# PIN_Gamma.net
KiCad netlist of a schematic drawn in Altium Designer
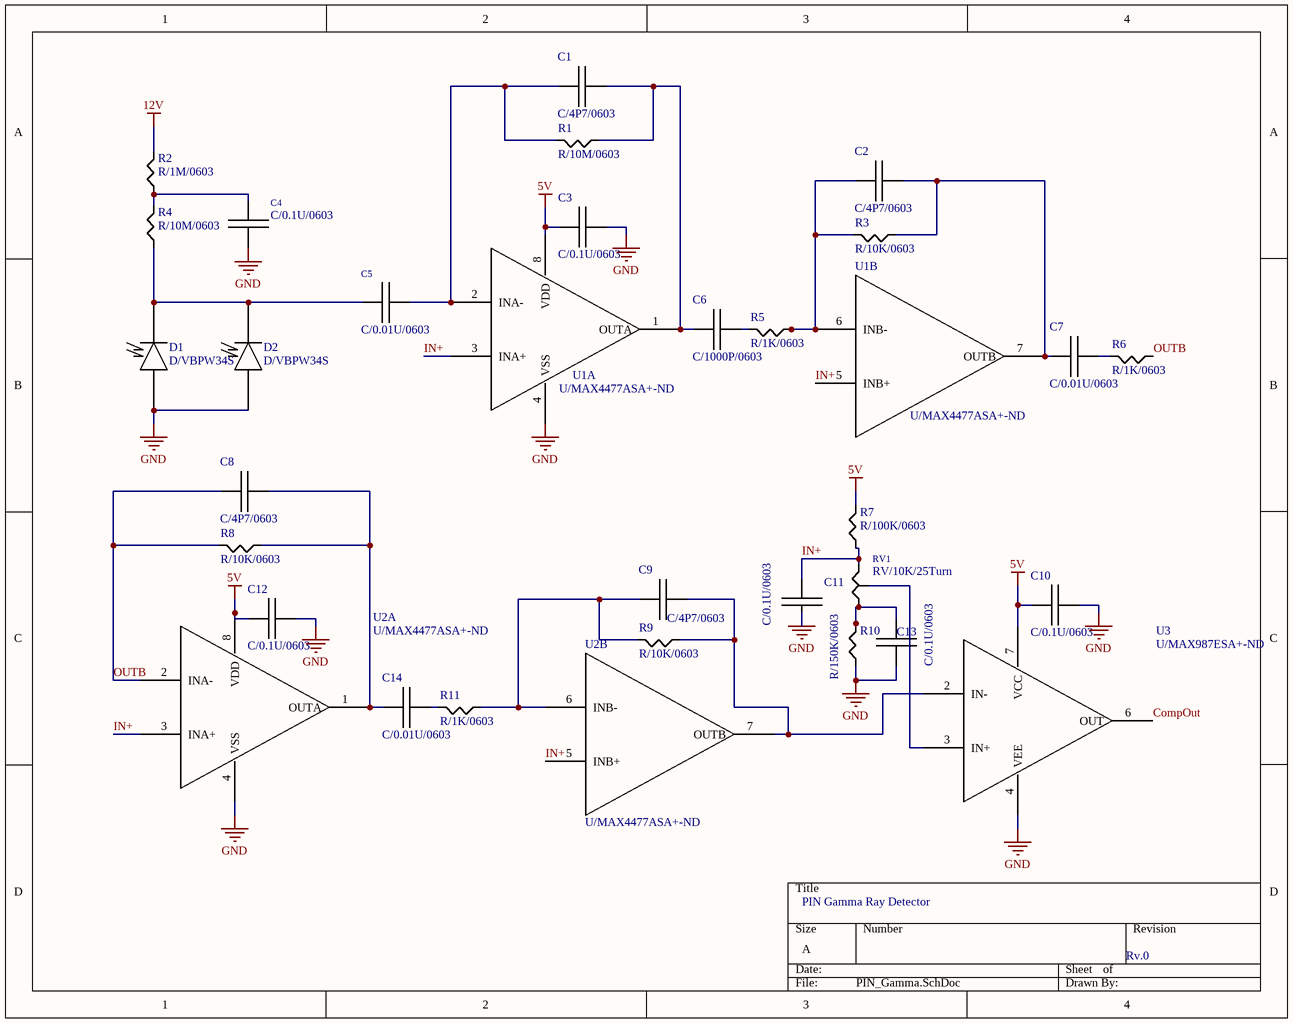
[diagram p0: PIN_Gamma.SchDoc]

(export (version "E")
  (design (tool "Eeschema 10.0.6"))
  (components
    (comp (ref "C1")
      (value "C/4P7/0603")
      (footprint "C/0603")
      (description "CAP CER 4.7PF 50V C0G/NPO 0603")
      (libsource (lib "Kyle_Sch_Lib") (part "C/4P7/0603"))
    )
    (comp (ref "C2")
      (value "C/4P7/0603")
      (footprint "C/0603")
      (description "CAP CER 4.7PF 50V C0G/NPO 0603")
      (libsource (lib "Kyle_Sch_Lib") (part "C/4P7/0603"))
    )
    (comp (ref "C3")
      (value "C/0.1U/0603")
      (footprint "C/0603")
      (description "CAP CER 0.1UF 50V X7R 0603")
      (fields (field (name "DIGIKEY PART") "399-7845-1-ND"))
      (libsource (lib "Kyle_Integrated_Library") (part "C/0.1U/0603"))
    )
    (comp (ref "C4")
      (value "C/0.1U/0603")
      (footprint "C/0603")
      (description "CAP CER 0.1UF 50V X7R 0603")
      (fields (field (name "DIGIKEY PART") "399-7845-1-ND"))
      (libsource (lib "Kyle_Integrated_Library") (part "C/0.1U/0603"))
    )
    (comp (ref "C5")
      (value "C/0.01U/0603")
      (footprint "C/0603")
      (description "CAP CER 0.01UF 50V X7R 0603")
      (fields (field (name "DIGIKEY PART") "399-1091-1-ND"))
      (libsource (lib "Kyle_Integrated_Library") (part "C/0.01U/0603"))
    )
    (comp (ref "C6")
      (value "C/1000P/0603")
      (footprint "C/0603")
      (description "CAP CER 1000PF 50V C0G/NP0 0603")
      (libsource (lib "Kyle_Integrated_Library") (part "C/1000P/0603"))
    )
    (comp (ref "C7")
      (value "C/0.01U/0603")
      (footprint "C/0603")
      (description "CAP CER 0.01UF 50V X7R 0603")
      (fields (field (name "DIGIKEY PART") "399-1091-1-ND"))
      (libsource (lib "Kyle_Sch_Lib") (part "C/0.01U/0603"))
    )
    (comp (ref "C8")
      (value "C/4P7/0603")
      (footprint "C/0603")
      (description "CAP CER 4.7PF 50V C0G/NPO 0603")
      (libsource (lib "Kyle_Sch_Lib") (part "C/4P7/0603"))
    )
    (comp (ref "C9")
      (value "C/4P7/0603")
      (footprint "C/0603")
      (description "CAP CER 4.7PF 50V C0G/NPO 0603")
      (libsource (lib "Kyle_Sch_Lib") (part "C/4P7/0603"))
    )
    (comp (ref "C10")
      (value "C/0.1U/0603")
      (footprint "C/0603")
      (description "CAP CER 0.1UF 50V X7R 0603")
      (fields (field (name "DIGIKEY PART") "399-7845-1-ND"))
      (libsource (lib "Kyle_Integrated_Library") (part "C/0.1U/0603"))
    )
    (comp (ref "C11")
      (value "C/0.1U/0603")
      (footprint "C/0603")
      (description "CAP CER 0.1UF 50V X7R 0603")
      (fields (field (name "DIGIKEY PART") "399-7845-1-ND"))
      (libsource (lib "Kyle_Integrated_Library") (part "C/0.1U/0603"))
    )
    (comp (ref "C12")
      (value "C/0.1U/0603")
      (footprint "C/0603")
      (description "CAP CER 0.1UF 50V X7R 0603")
      (fields (field (name "DIGIKEY PART") "399-7845-1-ND"))
      (libsource (lib "Kyle_Integrated_Library") (part "C/0.1U/0603"))
    )
    (comp (ref "C13")
      (value "C/0.1U/0603")
      (footprint "C/0603")
      (description "CAP CER 0.1UF 50V X7R 0603")
      (fields (field (name "DIGIKEY PART") "399-7845-1-ND"))
      (libsource (lib "Kyle_Integrated_Library") (part "C/0.1U/0603"))
    )
    (comp (ref "C14")
      (value "C/0.01U/0603")
      (footprint "C/0603")
      (description "CAP CER 0.01UF 50V X7R 0603")
      (fields (field (name "DIGIKEY PART") "399-1091-1-ND"))
      (libsource (lib "Kyle_Sch_Lib") (part "C/0.01U/0603"))
    )
    (comp (ref "D1")
      (value "D/VBPW34S")
      (footprint "VBPW34S")
      (description "PHOTODIODE PIN HI SPEED HI SENS")
      (libsource (lib "Kyle_Integrated_Library") (part "D/VBPW34S"))
    )
    (comp (ref "D2")
      (value "D/VBPW34S")
      (footprint "VBPW34S")
      (description "PHOTODIODE PIN HI SPEED HI SENS")
      (libsource (lib "Kyle_Integrated_Library") (part "D/VBPW34S"))
    )
    (comp (ref "R1")
      (value "R/10M/0603")
      (footprint "R/0603")
      (description "RES SMD 10M OHM 5% 1/10W 0603")
      (fields (field (name "DIGIKEY PART") "RMCF0603JT10M0CT-ND"))
      (libsource (lib "Kyle_Sch_Lib") (part "R/10M/0603"))
    )
    (comp (ref "R2")
      (value "R/1M/0603")
      (footprint "R/0603")
      (description "RES SMD 1M OHM 0.1% 1/16W 0603")
      (fields (field (name "DIGIKEY PART") "A119955CT-ND"))
      (libsource (lib "Kyle_Integrated_Library") (part "R/1M/0603"))
    )
    (comp (ref "R3")
      (value "R/10K/0603")
      (footprint "R/0603")
      (description "RES SMD 10K OHM 5% 1/10W 0603")
      (fields (field (name "DIGIKEY PART") "311-10KGRCT-ND"))
      (libsource (lib "Kyle_Integrated_Library") (part "R/10K/0603"))
    )
    (comp (ref "R4")
      (value "R/10M/0603")
      (footprint "R/0603")
      (description "RES SMD 10M OHM 5% 1/10W 0603")
      (fields (field (name "DIGIKEY PART") "RMCF0603JT10M0CT-ND"))
      (libsource (lib "Kyle_Sch_Lib") (part "R/10M/0603"))
    )
    (comp (ref "R5")
      (value "R/1K/0603")
      (footprint "R/0603")
      (description "RES SMD 1K OHM 5% 1/10W 0603")
      (fields (field (name "DIGIKEY PART") "311-1.0KGRCT-ND"))
      (libsource (lib "Kyle_Sch_Lib") (part "R/1K/0603"))
    )
    (comp (ref "R6")
      (value "R/1K/0603")
      (footprint "R/0603")
      (description "RES SMD 1K OHM 5% 1/10W 0603")
      (fields (field (name "DIGIKEY PART") "311-1.0KGRCT-ND"))
      (libsource (lib "Kyle_Sch_Lib") (part "R/1K/0603"))
    )
    (comp (ref "R7")
      (value "R/100K/0603")
      (footprint "R/0603")
      (description "RES SMD 100K OHM 1% 1/10W 0603")
      (fields (field (name "DIGIKEY PART") "311-100KHRCT-ND"))
      (libsource (lib "Kyle_Integrated_Library") (part "R/100K/0603"))
    )
    (comp (ref "R8")
      (value "R/10K/0603")
      (footprint "R/0603")
      (description "RES SMD 10K OHM 5% 1/10W 0603")
      (fields (field (name "DIGIKEY PART") "311-10KGRCT-ND"))
      (libsource (lib "Kyle_Integrated_Library") (part "R/10K/0603"))
    )
    (comp (ref "R9")
      (value "R/10K/0603")
      (footprint "R/0603")
      (description "RES SMD 10K OHM 5% 1/10W 0603")
      (fields (field (name "DIGIKEY PART") "311-10KGRCT-ND"))
      (libsource (lib "Kyle_Integrated_Library") (part "R/10K/0603"))
    )
    (comp (ref "R10")
      (value "R/150K/0603")
      (footprint "R/0603")
      (description "RES SMD 150K OHM 1% 1/10W 0603")
      (fields (field (name "DIGIKEY PART") "311-150KGRDKR-ND"))
      (libsource (lib "Kyle_Integrated_Library") (part "R/150K/0603"))
    )
    (comp (ref "R11")
      (value "R/1K/0603")
      (footprint "R/0603")
      (description "RES SMD 1K OHM 5% 1/10W 0603")
      (fields (field (name "DIGIKEY PART") "311-1.0KGRCT-ND"))
      (libsource (lib "Kyle_Sch_Lib") (part "R/1K/0603"))
    )
    (comp (ref "RV1")
      (value "RV/10K/25Turn")
      (footprint "10K/25TN")
      (description "TRIMMER 10K OHM 0.5W TH")
      (fields (field (name "DIGIKEY PART") "A105870-ND"))
      (libsource (lib "Kyle_Integrated_Library") (part "RV/10K/25Turn"))
    )
    (comp (ref "U1")
      (value "U/MAX4477ASA+-ND")
      (footprint "SO8")
      (description "Dual Low-Noise, Low-Distortion, Wide-Band, Rail-to-Rail Op Amps")
      (libsource (lib "Kyle_Integrated_Library") (part "U/MAX4477ASA+-ND"))
    )
    (comp (ref "U2")
      (value "U/MAX4477ASA+-ND")
      (footprint "SO8")
      (description "Dual Low-Noise, Low-Distortion, Wide-Band, Rail-to-Rail Op Amps")
      (libsource (lib "Kyle_Integrated_Library") (part "U/MAX4477ASA+-ND"))
    )
    (comp (ref "U3")
      (value "U/MAX987ESA+-ND")
      (footprint "SO8")
      (description "Comparator General Purpose CMOS, Push-Pull, Rail-to-Rail, TTL 8-SO")
      (libsource (lib "Kyle_Integrated_Library") (part "U/MAX987ESA+-ND"))
    )
  )
  (nets
    (net (code "1") (name "/CompOut") (class "Default")
      (node (ref "U3") (pin "6") (pinfunction "OUT_6") (pintype "passive"))
    )
    (net (code "2") (name "/IN+") (class "Default")
      (node (ref "C11") (pin "1") (pinfunction "1_1") (pintype "passive"))
      (node (ref "R7") (pin "2") (pinfunction "2_2") (pintype "passive"))
      (node (ref "RV1") (pin "1") (pinfunction "1_1") (pintype "passive"))
      (node (ref "U1") (pin "3") (pinfunction "INA+_3") (pintype "passive"))
      (node (ref "U1") (pin "5") (pinfunction "INB+_5") (pintype "passive"))
      (node (ref "U2") (pin "3") (pinfunction "INA+_3") (pintype "passive"))
      (node (ref "U2") (pin "5") (pinfunction "INB+_5") (pintype "passive"))
    )
    (net (code "3") (name "/OUTB") (class "Default")
      (node (ref "C8") (pin "1") (pinfunction "1_1") (pintype "passive"))
      (node (ref "R6") (pin "2") (pinfunction "2_2") (pintype "passive"))
      (node (ref "R8") (pin "1") (pinfunction "1_1") (pintype "passive"))
      (node (ref "U2") (pin "2") (pinfunction "INA-_2") (pintype "passive"))
    )
    (net (code "4") (name "5V") (class "Default")
      (node (ref "C10") (pin "1") (pinfunction "1_1") (pintype "passive"))
      (node (ref "C12") (pin "1") (pinfunction "1_1") (pintype "passive"))
      (node (ref "C3") (pin "1") (pinfunction "1_1") (pintype "passive"))
      (node (ref "R7") (pin "1") (pinfunction "1_1") (pintype "passive"))
      (node (ref "U1") (pin "8") (pinfunction "VDD_8") (pintype "power_in"))
      (node (ref "U2") (pin "8") (pinfunction "VDD_8") (pintype "power_in"))
      (node (ref "U3") (pin "7") (pinfunction "VCC_7") (pintype "power_in"))
    )
    (net (code "5") (name "12V") (class "Default")
      (node (ref "R2") (pin "1") (pinfunction "1_1") (pintype "passive"))
    )
    (net (code "6") (name "GND") (class "Default")
      (node (ref "C10") (pin "2") (pinfunction "2_2") (pintype "passive"))
      (node (ref "C11") (pin "2") (pinfunction "2_2") (pintype "passive"))
      (node (ref "C12") (pin "2") (pinfunction "2_2") (pintype "passive"))
      (node (ref "C13") (pin "2") (pinfunction "2_2") (pintype "passive"))
      (node (ref "C3") (pin "2") (pinfunction "2_2") (pintype "passive"))
      (node (ref "C4") (pin "2") (pinfunction "2_2") (pintype "passive"))
      (node (ref "D1") (pin "A") (pinfunction "A_A") (pintype "passive"))
      (node (ref "D2") (pin "A") (pinfunction "A_A") (pintype "passive"))
      (node (ref "R10") (pin "2") (pinfunction "2_2") (pintype "passive"))
      (node (ref "U1") (pin "4") (pinfunction "VSS_4") (pintype "power_in"))
      (node (ref "U2") (pin "4") (pinfunction "VSS_4") (pintype "power_in"))
      (node (ref "U3") (pin "4") (pinfunction "VEE_4") (pintype "power_in"))
    )
    (net (code "7") (name "Net-(C4-Pad1)") (class "Default")
      (node (ref "C4") (pin "1") (pinfunction "1_1") (pintype "passive"))
      (node (ref "R2") (pin "2") (pinfunction "2_2") (pintype "passive"))
      (node (ref "R4") (pin "1") (pinfunction "1_1") (pintype "passive"))
    )
    (net (code "8") (name "Net-(C5-Pad1)") (class "Default")
      (node (ref "C5") (pin "1") (pinfunction "1_1") (pintype "passive"))
      (node (ref "D1") (pin "K") (pinfunction "K_K") (pintype "passive"))
      (node (ref "D2") (pin "K") (pinfunction "K_K") (pintype "passive"))
      (node (ref "R4") (pin "2") (pinfunction "2_2") (pintype "passive"))
    )
    (net (code "9") (name "Net-(C6-Pad2)") (class "Default")
      (node (ref "C6") (pin "2") (pinfunction "2_2") (pintype "passive"))
      (node (ref "R5") (pin "1") (pinfunction "1_1") (pintype "passive"))
    )
    (net (code "10") (name "Net-(C7-Pad2)") (class "Default")
      (node (ref "C7") (pin "2") (pinfunction "2_2") (pintype "passive"))
      (node (ref "R6") (pin "1") (pinfunction "1_1") (pintype "passive"))
    )
    (net (code "11") (name "Net-(C13-Pad1)") (class "Default")
      (node (ref "C13") (pin "1") (pinfunction "1_1") (pintype "passive"))
      (node (ref "R10") (pin "1") (pinfunction "1_1") (pintype "passive"))
      (node (ref "RV1") (pin "3") (pinfunction "3_3") (pintype "passive"))
    )
    (net (code "12") (name "Net-(C14-Pad2)") (class "Default")
      (node (ref "C14") (pin "2") (pinfunction "2_2") (pintype "passive"))
      (node (ref "R11") (pin "1") (pinfunction "1_1") (pintype "passive"))
    )
    (net (code "13") (name "Net-(U1A-INA-)") (class "Default")
      (node (ref "C1") (pin "1") (pinfunction "1_1") (pintype "passive"))
      (node (ref "C5") (pin "2") (pinfunction "2_2") (pintype "passive"))
      (node (ref "R1") (pin "1") (pinfunction "1_1") (pintype "passive"))
      (node (ref "U1") (pin "2") (pinfunction "INA-_2") (pintype "passive"))
    )
    (net (code "14") (name "Net-(U1A-OUTA)") (class "Default")
      (node (ref "C1") (pin "2") (pinfunction "2_2") (pintype "passive"))
      (node (ref "C6") (pin "1") (pinfunction "1_1") (pintype "passive"))
      (node (ref "R1") (pin "2") (pinfunction "2_2") (pintype "passive"))
      (node (ref "U1") (pin "1") (pinfunction "OUTA_1") (pintype "passive"))
    )
    (net (code "15") (name "Net-(U1B-INB-)") (class "Default")
      (node (ref "C2") (pin "1") (pinfunction "1_1") (pintype "passive"))
      (node (ref "R3") (pin "1") (pinfunction "1_1") (pintype "passive"))
      (node (ref "R5") (pin "2") (pinfunction "2_2") (pintype "passive"))
      (node (ref "U1") (pin "6") (pinfunction "INB-_6") (pintype "passive"))
    )
    (net (code "16") (name "Net-(U1B-OUTB)") (class "Default")
      (node (ref "C2") (pin "2") (pinfunction "2_2") (pintype "passive"))
      (node (ref "C7") (pin "1") (pinfunction "1_1") (pintype "passive"))
      (node (ref "R3") (pin "2") (pinfunction "2_2") (pintype "passive"))
      (node (ref "U1") (pin "7") (pinfunction "OUTB_7") (pintype "passive"))
    )
    (net (code "17") (name "Net-(U2A-OUTA)") (class "Default")
      (node (ref "C14") (pin "1") (pinfunction "1_1") (pintype "passive"))
      (node (ref "C8") (pin "2") (pinfunction "2_2") (pintype "passive"))
      (node (ref "R8") (pin "2") (pinfunction "2_2") (pintype "passive"))
      (node (ref "U2") (pin "1") (pinfunction "OUTA_1") (pintype "passive"))
    )
    (net (code "18") (name "Net-(U2B-INB-)") (class "Default")
      (node (ref "C9") (pin "1") (pinfunction "1_1") (pintype "passive"))
      (node (ref "R11") (pin "2") (pinfunction "2_2") (pintype "passive"))
      (node (ref "R9") (pin "1") (pinfunction "1_1") (pintype "passive"))
      (node (ref "U2") (pin "6") (pinfunction "INB-_6") (pintype "passive"))
    )
    (net (code "19") (name "Net-(U2B-OUTB)") (class "Default")
      (node (ref "C9") (pin "2") (pinfunction "2_2") (pintype "passive"))
      (node (ref "R9") (pin "2") (pinfunction "2_2") (pintype "passive"))
      (node (ref "U2") (pin "7") (pinfunction "OUTB_7") (pintype "passive"))
      (node (ref "U3") (pin "2") (pinfunction "IN-_2") (pintype "passive"))
    )
    (net (code "20") (name "Net-(U3-IN+)") (class "Default")
      (node (ref "RV1") (pin "2") (pinfunction "2_2") (pintype "passive"))
      (node (ref "U3") (pin "3") (pinfunction "IN+_3") (pintype "passive"))
    )
    (net (code "21") (name "unconnected-(U3-NC-Pad1)") (class "Default")
      (node (ref "U3") (pin "1") (pinfunction "NC_1") (pintype "passive"))
    )
    (net (code "22") (name "unconnected-(U3-NC-Pad5)") (class "Default")
      (node (ref "U3") (pin "5") (pinfunction "NC_5") (pintype "passive"))
    )
    (net (code "23") (name "unconnected-(U3-NC-Pad8)") (class "Default")
      (node (ref "U3") (pin "8") (pinfunction "NC_8") (pintype "passive"))
    )
  )
)
